# Shield_Dropscreen_LED_V_0_0.net
KiCad netlist of a schematic drawn in EasyEDA
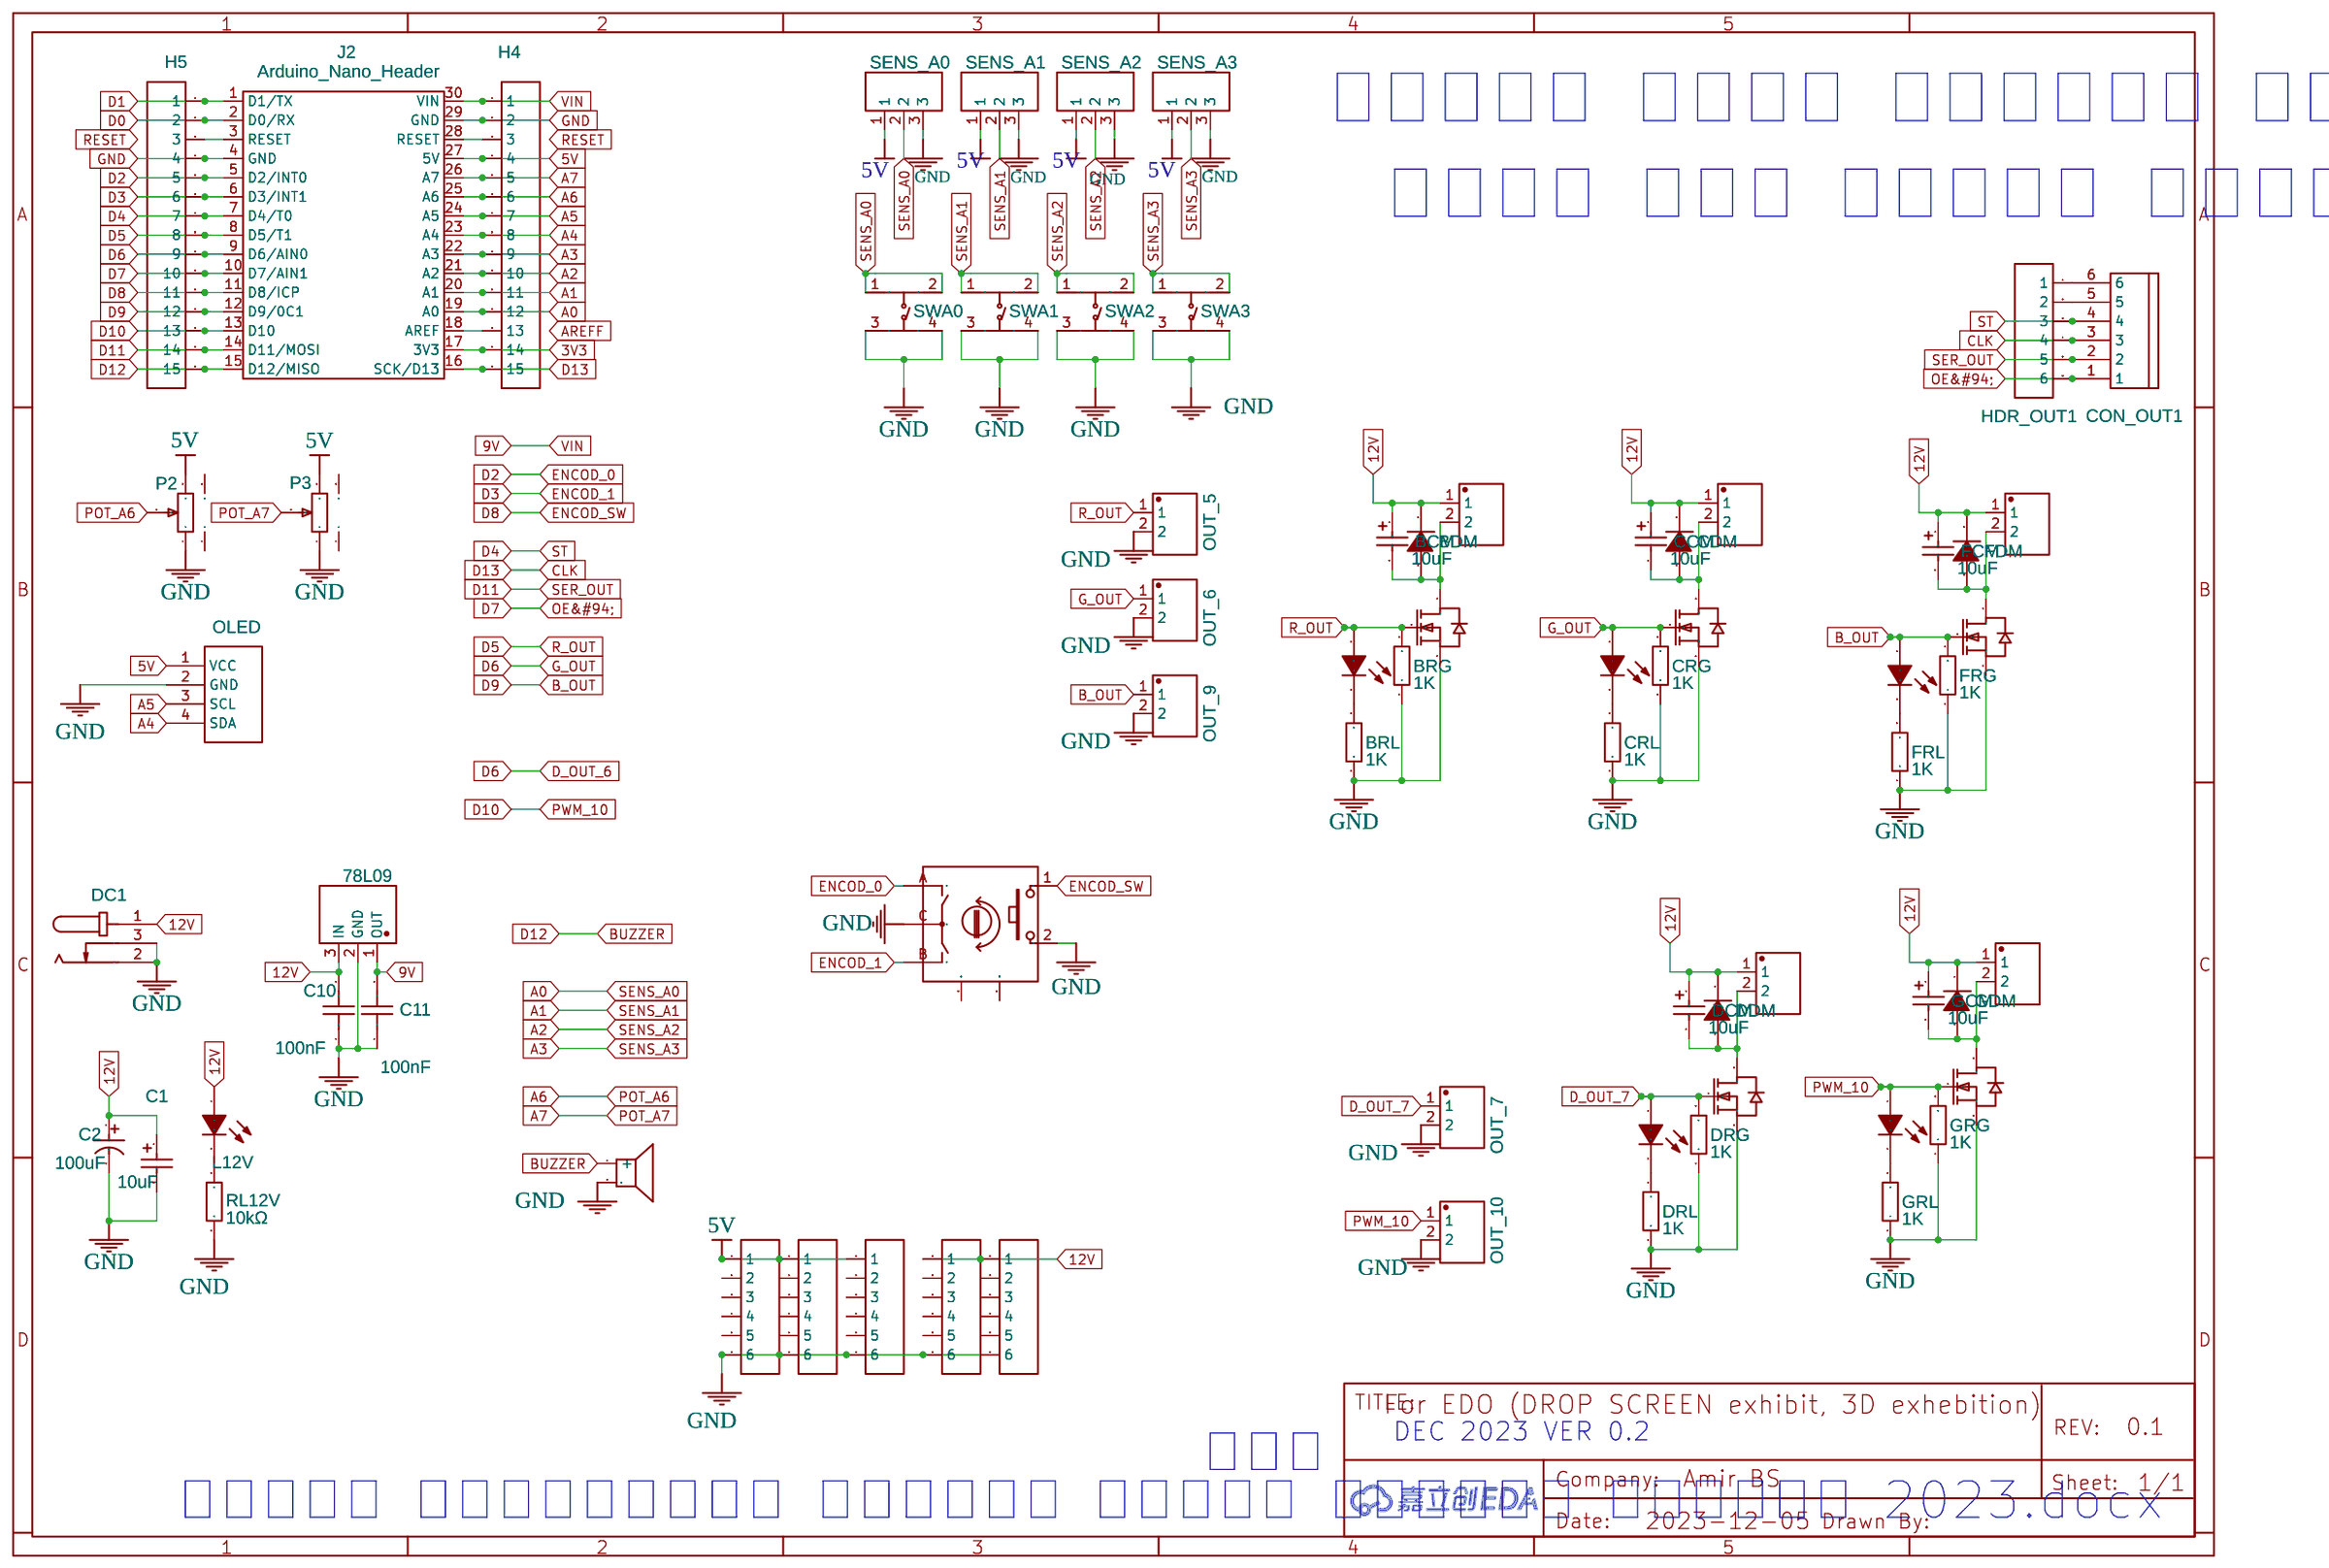
[diagram p0: schematic sheet]

(export (version "E")
  (design (tool "Eeschema 10.0.6"))
  (components
    (comp (ref "BCM")
      (value "10uF")
      (fields (field (name "Manufacturer Part") "TAJA106K016RNJ") (field (name "Manufacturer") "Kyocera AVX"))
      (libsource (lib "") (part "TAJA106K016RNJ"))
    )
    (comp (ref "BCON")
      (value "KF2510-2A")
      (fields (field (name "BOM_Supplier Part") "C27543"))
      (libsource (lib "") (part "KF2510-2A_1"))
    )
    (comp (ref "BDM")
      (value "1N4007")
      (fields (field (name "BOM_Manufacturer Part") "1N4007F") (field (name "BOM_Supplier Part") "C110856"))
      (libsource (lib "") (part "1N4007F_2"))
    )
    (comp (ref "BLD")
      (value "LED")
      (fields
        (field (name "BOM_Manufacturer Part") "19-217/BHC-ZL1M2RY/3T")
        (field (name "BOM_Supplier Part") "C72041")
      )
      (libsource (lib "") (part "19-217/BHC-ZL1M2RY/3T_3"))
    )
    (comp (ref "BQ")
      (value "Q")
      (fields (field (name "BOM_Manufacturer Part") "AO3400") (field (name "BOM_Supplier Part") "C5224189"))
      (libsource (lib "") (part "JSM2302_4"))
    )
    (comp (ref "BRG")
      (value "1K")
      (fields
        (field (name "BOM_Manufacturer Part") "0603WAF1001T5E")
        (field (name "BOM_Supplier Part") "C21190")
      )
      (libsource (lib "") (part "0603WAF1001T5E"))
    )
    (comp (ref "BRL")
      (value "1K")
      (fields
        (field (name "BOM_Manufacturer Part") "0603WAF1001T5E")
        (field (name "BOM_Supplier Part") "C21190")
      )
      (libsource (lib "") (part "0603WAF1001T5E_8"))
    )
    (comp (ref "BUZZER1")
      (value "BUZZER-12X9")
      (fields (field (name "Manufacturer Part") "buzzer-12X9"))
      (libsource (lib "") (part "BUZZER-12X9"))
    )
    (comp (ref "C1")
      (value "10uF")
      (fields (field (name "Manufacturer Part") "TAJA106K016RNJ") (field (name "Manufacturer") "Kyocera AVX"))
      (libsource (lib "") (part "TAJA106K016RNJ_4"))
    )
    (comp (ref "C2")
      (value "100uF")
      (fields
        (field (name "Manufacturer Part") "KM107M035E11RR0VH2FP0")
        (field (name "Manufacturer") "CX(承兴)")
      )
      (libsource (lib "") (part "100uF 35V 6.3*11"))
    )
    (comp (ref "C10")
      (value "100nF")
      (fields
        (field (name "Manufacturer Part") "CC0603KRX7R9BB104")
        (field (name "Manufacturer") "YAGEO(国巨)")
      )
      (libsource (lib "") (part "CC0603KRX7R9BB104"))
    )
    (comp (ref "C11")
      (value "100nF")
      (fields
        (field (name "Manufacturer Part") "CC0603KRX7R9BB104")
        (field (name "Manufacturer") "YAGEO(国巨)")
      )
      (libsource (lib "") (part "CC0603KRX7R9BB104"))
    )
    (comp (ref "CCM")
      (value "10uF")
      (fields (field (name "Manufacturer Part") "TAJA106K016RNJ") (field (name "Manufacturer") "Kyocera AVX"))
      (libsource (lib "") (part "TAJA106K016RNJ_3"))
    )
    (comp (ref "CCON")
      (value "KF2510-2A")
      (fields (field (name "BOM_Supplier Part") "C27543"))
      (libsource (lib "") (part "KF2510-2A_5"))
    )
    (comp (ref "CDM")
      (value "1N4007")
      (fields (field (name "BOM_Manufacturer Part") "1N4007F") (field (name "BOM_Supplier Part") "C110856"))
      (libsource (lib "") (part "1N4007F_3"))
    )
    (comp (ref "CLD")
      (value "LED")
      (fields
        (field (name "BOM_Manufacturer Part") "19-217/BHC-ZL1M2RY/3T")
        (field (name "BOM_Supplier Part") "C72041")
      )
      (libsource (lib "") (part "19-217/BHC-ZL1M2RY/3T"))
    )
    (comp (ref "CON_OUT1")
      (value "CON6")
      (fields (field (name "BOM_Manufacturer Part") "XH-6AW") (field (name "BOM_Supplier Part") "C8876"))
      (libsource (lib "") (part "XH-6AW_C8876"))
    )
    (comp (ref "CQ")
      (value "Q")
      (fields (field (name "BOM_Manufacturer Part") "AO3400") (field (name "BOM_Supplier Part") "C5224189"))
      (libsource (lib "") (part "JSM2302"))
    )
    (comp (ref "CRG")
      (value "1K")
      (fields
        (field (name "BOM_Manufacturer Part") "0603WAF1001T5E")
        (field (name "BOM_Supplier Part") "C21190")
      )
      (libsource (lib "") (part "0603WAF1001T5E_1"))
    )
    (comp (ref "CRL")
      (value "1K")
      (fields
        (field (name "BOM_Manufacturer Part") "0603WAF1001T5E")
        (field (name "BOM_Supplier Part") "C21190")
      )
      (libsource (lib "") (part "0603WAF1001T5E_7"))
    )
    (comp (ref "DC1")
      (value "DC")
      (fields
        (field (name "BOM_Manufacturer Part") "DC005-2.0MM")
        (field (name "BOM_Supplier Part") "C111567")
      )
      (libsource (lib "") (part "DC005-2.0MM"))
    )
    (comp (ref "DCM")
      (value "10uF")
      (fields (field (name "Manufacturer Part") "TAJA106K016RNJ") (field (name "Manufacturer") "Kyocera AVX"))
      (libsource (lib "") (part "TAJA106K016RNJ_1"))
    )
    (comp (ref "DCON")
      (value "KF2510-2A")
      (fields (field (name "BOM_Supplier Part") "C27543"))
      (libsource (lib "") (part "KF2510-2A_3"))
    )
    (comp (ref "DDM")
      (value "1N4007")
      (fields (field (name "BOM_Manufacturer Part") "1N4007F") (field (name "BOM_Supplier Part") "C110856"))
      (libsource (lib "") (part "1N4007F"))
    )
    (comp (ref "DLD")
      (value "LED")
      (fields
        (field (name "BOM_Manufacturer Part") "19-217/BHC-ZL1M2RY/3T")
        (field (name "BOM_Supplier Part") "C72041")
      )
      (libsource (lib "") (part "19-217/BHC-ZL1M2RY/3T_5"))
    )
    (comp (ref "DQ")
      (value "Q")
      (fields (field (name "BOM_Manufacturer Part") "AO3400") (field (name "BOM_Supplier Part") "C5224189"))
      (libsource (lib "") (part "JSM2302_2"))
    )
    (comp (ref "DRG")
      (value "1K")
      (fields
        (field (name "BOM_Manufacturer Part") "0603WAF1001T5E")
        (field (name "BOM_Supplier Part") "C21190")
      )
      (libsource (lib "") (part "0603WAF1001T5E_3"))
    )
    (comp (ref "DRL")
      (value "1K")
      (fields
        (field (name "BOM_Manufacturer Part") "0603WAF1001T5E")
        (field (name "BOM_Supplier Part") "C21190")
      )
      (libsource (lib "") (part "0603WAF1001T5E_4"))
    )
    (comp (ref "FCM")
      (value "10uF")
      (fields (field (name "Manufacturer Part") "TAJA106K016RNJ") (field (name "Manufacturer") "Kyocera AVX"))
      (libsource (lib "") (part "TAJA106K016RNJ_2"))
    )
    (comp (ref "FCON")
      (value "KF2510-2A")
      (fields (field (name "BOM_Supplier Part") "C27543"))
      (libsource (lib "") (part "KF2510-2A_2"))
    )
    (comp (ref "FDM")
      (value "1N4007")
      (fields (field (name "BOM_Manufacturer Part") "1N4007F") (field (name "BOM_Supplier Part") "C110856"))
      (libsource (lib "") (part "1N4007F_4"))
    )
    (comp (ref "FLD")
      (value "LED")
      (fields
        (field (name "BOM_Manufacturer Part") "19-217/BHC-ZL1M2RY/3T")
        (field (name "BOM_Supplier Part") "C72041")
      )
      (libsource (lib "") (part "19-217/BHC-ZL1M2RY/3T_1"))
    )
    (comp (ref "FQ")
      (value "Q")
      (fields (field (name "BOM_Manufacturer Part") "AO3400") (field (name "BOM_Supplier Part") "C5224189"))
      (libsource (lib "") (part "JSM2302_1"))
    )
    (comp (ref "FRG")
      (value "1K")
      (fields
        (field (name "BOM_Manufacturer Part") "0603WAF1001T5E")
        (field (name "BOM_Supplier Part") "C21190")
      )
      (libsource (lib "") (part "0603WAF1001T5E_9"))
    )
    (comp (ref "FRL")
      (value "1K")
      (fields
        (field (name "BOM_Manufacturer Part") "0603WAF1001T5E")
        (field (name "BOM_Supplier Part") "C21190")
      )
      (libsource (lib "") (part "0603WAF1001T5E_2"))
    )
    (comp (ref "GCM")
      (value "10uF")
      (fields (field (name "Manufacturer Part") "TAJA106K016RNJ") (field (name "Manufacturer") "Kyocera AVX"))
      (libsource (lib "") (part "TAJA106K016RNJ_5"))
    )
    (comp (ref "GCON")
      (value "KF2510-2A")
      (fields (field (name "BOM_Supplier Part") "C27543"))
      (libsource (lib "") (part "KF2510-2A"))
    )
    (comp (ref "GDM")
      (value "1N4007")
      (fields (field (name "BOM_Manufacturer Part") "1N4007F") (field (name "BOM_Supplier Part") "C110856"))
      (libsource (lib "") (part "1N4007F_1"))
    )
    (comp (ref "GLD")
      (value "LED")
      (fields
        (field (name "BOM_Manufacturer Part") "19-217/BHC-ZL1M2RY/3T")
        (field (name "BOM_Supplier Part") "C72041")
      )
      (libsource (lib "") (part "19-217/BHC-ZL1M2RY/3T_4"))
    )
    (comp (ref "GQ")
      (value "Q")
      (fields (field (name "BOM_Manufacturer Part") "AO3400") (field (name "BOM_Supplier Part") "C5224189"))
      (libsource (lib "") (part "JSM2302_3"))
    )
    (comp (ref "GRG")
      (value "1K")
      (fields
        (field (name "BOM_Manufacturer Part") "0603WAF1001T5E")
        (field (name "BOM_Supplier Part") "C21190")
      )
      (libsource (lib "") (part "0603WAF1001T5E_5"))
    )
    (comp (ref "GRL")
      (value "1K")
      (fields
        (field (name "BOM_Manufacturer Part") "0603WAF1001T5E")
        (field (name "BOM_Supplier Part") "C21190")
      )
      (libsource (lib "") (part "0603WAF1001T5E_6"))
    )
    (comp (ref "H1")
      (value "HDR-F-2.54_1x6")
      (fields (field (name "BOM_Supplier Part") "C40877"))
      (libsource (lib "") (part "HDR-F-2.54_1x6"))
    )
    (comp (ref "H2")
      (value "HDR-F-2.54_1x6")
      (fields (field (name "BOM_Supplier Part") "C40877"))
      (libsource (lib "") (part "HDR-F-2.54_1x6"))
    )
    (comp (ref "H3")
      (value "HDR-F-2.54_1x6")
      (fields (field (name "BOM_Supplier Part") "C40877"))
      (libsource (lib "") (part "HDR-F-2.54_1x6"))
    )
    (comp (ref "H4")
      (value "HDR-F-2.54_1x15")
      (fields (field (name "BOM_Supplier Part") "C124408"))
      (libsource (lib "") (part "HDR-F-2.54_1x15_1"))
    )
    (comp (ref "H5")
      (value "HDR-F-2.54_1x15")
      (fields (field (name "BOM_Supplier Part") "C124408"))
      (libsource (lib "") (part "HDR-F-2.54_1x15"))
    )
    (comp (ref "H6")
      (value "HDR-F-2.54_1x6")
      (fields (field (name "BOM_Supplier Part") "C40877"))
      (libsource (lib "") (part "HDR-F-2.54_1x6"))
    )
    (comp (ref "H11")
      (value "HDR-F-2.54_1x6")
      (fields (field (name "BOM_Supplier Part") "C40877"))
      (libsource (lib "") (part "HDR-F-2.54_1x6"))
    )
    (comp (ref "HDR_OUT1")
      (value "HDR6")
      (fields (field (name "BOM_Supplier Part") "C190819"))
      (libsource (lib "") (part "HDR-M-2.54_1x6"))
    )
    (comp (ref "J2") (value "Arduino_Nano_Header") (libsource (lib "") (part "Arduino_Nano_Header")))
    (comp (ref "L12V")
      (value "LED")
      (fields
        (field (name "BOM_Manufacturer Part") "19-217/BHC-ZL1M2RY/3T")
        (field (name "BOM_Supplier Part") "C72041")
      )
      (libsource (lib "") (part "19-217/BHC-ZL1M2RY/3T_2"))
    )
    (comp (ref "OLED")
      (value "1.3 inch OLED SSH1106 I2C 128x64 copy")
      (libsource (lib "") (part "1.3 inch OLED SSH1106 I2C 128x64 copy"))
    )
    (comp (ref "OUT_5")
      (value "KF2510-2A")
      (fields (field (name "BOM_Supplier Part") "C27543"))
      (libsource (lib "") (part "KF2510-2A_4"))
    )
    (comp (ref "OUT_6")
      (value "KF2510-2A")
      (fields (field (name "BOM_Supplier Part") "C27543"))
      (libsource (lib "") (part "KF2510-2A_4"))
    )
    (comp (ref "OUT_7")
      (value "KF2510-2A")
      (fields (field (name "BOM_Supplier Part") "C27543"))
      (libsource (lib "") (part "KF2510-2A_4"))
    )
    (comp (ref "OUT_9")
      (value "KF2510-2A")
      (fields (field (name "BOM_Supplier Part") "C27543"))
      (libsource (lib "") (part "KF2510-2A_4"))
    )
    (comp (ref "OUT_10")
      (value "KF2510-2A")
      (fields (field (name "BOM_Supplier Part") "C27543"))
      (libsource (lib "") (part "KF2510-2A_4"))
    )
    (comp (ref "P2")
      (value "长柄旋转电位器")
      (fields (field (name "BOM_Supplier Part") "C2874842"))
      (libsource (lib "") (part "长柄旋转电位器"))
    )
    (comp (ref "P3")
      (value "长柄旋转电位器")
      (fields (field (name "BOM_Supplier Part") "C2874842"))
      (libsource (lib "") (part "长柄旋转电位器"))
    )
    (comp (ref "RL12V")
      (value "10kΩ")
      (fields
        (field (name "BOM_Manufacturer Part") "0603WAF1002T5E")
        (field (name "BOM_Supplier Part") "C25804")
      )
      (libsource (lib "") (part "0603WAF1002T5E"))
    )
    (comp (ref "SENS_A0")
      (value "FK2510")
      (fields (field (name "Manufacturer Part") "2510-3A") (field (name "Manufacturer") "BOOMELE(博穆精密)"))
      (libsource (lib "") (part "kf2510_3A"))
    )
    (comp (ref "SENS_A1")
      (value "FK2510")
      (fields (field (name "Manufacturer Part") "2510-3A") (field (name "Manufacturer") "BOOMELE(博穆精密)"))
      (libsource (lib "") (part "kf2510_3A"))
    )
    (comp (ref "SENS_A2")
      (value "FK2510")
      (fields (field (name "Manufacturer Part") "2510-3A") (field (name "Manufacturer") "BOOMELE(博穆精密)"))
      (libsource (lib "") (part "kf2510_3A"))
    )
    (comp (ref "SENS_A3")
      (value "FK2510")
      (fields (field (name "Manufacturer Part") "2510-3A") (field (name "Manufacturer") "BOOMELE(博穆精密)"))
      (libsource (lib "") (part "kf2510_3A"))
    )
    (comp (ref "SW1")
      (value "PEC11R-4015F-S0024")
      (fields (field (name "Manufacturer") "BOURNS"))
      (libsource (lib "") (part "PEC11R-4015F-S0024"))
    )
    (comp (ref "SWA0")
      (value "TC-6610-7-160G")
      (fields (field (name "Manufacturer") "HCTL(华灿天禄)"))
      (libsource (lib "") (part "TC-6610-7-160G"))
    )
    (comp (ref "SWA1")
      (value "TC-6610-7-160G")
      (fields (field (name "Manufacturer") "HCTL(华灿天禄)"))
      (libsource (lib "") (part "TC-6610-7-160G"))
    )
    (comp (ref "SWA2")
      (value "TC-6610-7-160G")
      (fields (field (name "Manufacturer") "HCTL(华灿天禄)"))
      (libsource (lib "") (part "TC-6610-7-160G"))
    )
    (comp (ref "SWA3")
      (value "TC-6610-7-160G")
      (fields (field (name "Manufacturer") "HCTL(华灿天禄)"))
      (libsource (lib "") (part "TC-6610-7-160G"))
    )
    (comp (ref "U5")
      (value "78L09")
      (fields (field (name "Manufacturer Part") "78L09U 78L09") (field (name "Manufacturer") "CBI(创基)"))
      (libsource (lib "") (part "78L09U 78L09"))
    )
  )
  (nets
    (net (code "1") (name "3V3") (class "Default")
      (node (ref "H4") (pin "14") (pinfunction "14_14") (pintype "unspecified"))
      (node (ref "J2") (pin "17") (pinfunction "3V3_17") (pintype "unspecified"))
    )
    (net (code "2") (name "5V") (class "Default")
      (node (ref "H1") (pin "1") (pinfunction "1_1") (pintype "input"))
      (node (ref "H2") (pin "1") (pinfunction "1_1") (pintype "input"))
      (node (ref "H3") (pin "1") (pinfunction "1_1") (pintype "input"))
      (node (ref "H4") (pin "4") (pinfunction "4_4") (pintype "unspecified"))
      (node (ref "J2") (pin "27") (pinfunction "5V_27") (pintype "unspecified"))
      (node (ref "OLED") (pin "1") (pinfunction "VCC_1") (pintype "passive"))
      (node (ref "P2") (pin "3") (pinfunction "3_3") (pintype "input"))
      (node (ref "P3") (pin "3") (pinfunction "3_3") (pintype "input"))
      (node (ref "SENS_A0") (pin "1") (pinfunction "1_1") (pintype "unspecified"))
      (node (ref "SENS_A1") (pin "1") (pinfunction "1_1") (pintype "unspecified"))
      (node (ref "SENS_A2") (pin "1") (pinfunction "1_1") (pintype "unspecified"))
      (node (ref "SENS_A3") (pin "1") (pinfunction "1_1") (pintype "unspecified"))
    )
    (net (code "3") (name "9V") (class "Default")
      (node (ref "C11") (pin "2") (pinfunction "2_2") (pintype "unspecified"))
      (node (ref "H4") (pin "1") (pinfunction "1_1") (pintype "unspecified"))
      (node (ref "J2") (pin "30") (pinfunction "VIN_30") (pintype "unspecified"))
      (node (ref "U5") (pin "1") (pinfunction "OUT_1") (pintype "unspecified"))
    )
    (net (code "4") (name "12V") (class "Default")
      (node (ref "BCM") (pin "1") (pinfunction "1_1") (pintype "input"))
      (node (ref "BCON") (pin "1") (pinfunction "1_1") (pintype "unspecified"))
      (node (ref "BDM") (pin "1") (pinfunction "C_1") (pintype "unspecified"))
      (node (ref "C1") (pin "1") (pinfunction "1_1") (pintype "input"))
      (node (ref "C10") (pin "2") (pinfunction "2_2") (pintype "unspecified"))
      (node (ref "C2") (pin "1") (pinfunction "1_1") (pintype "input"))
      (node (ref "CCM") (pin "1") (pinfunction "1_1") (pintype "input"))
      (node (ref "CCON") (pin "1") (pinfunction "1_1") (pintype "unspecified"))
      (node (ref "CDM") (pin "1") (pinfunction "C_1") (pintype "unspecified"))
      (node (ref "DC1") (pin "1") (pinfunction "1_1") (pintype "unspecified"))
      (node (ref "DCM") (pin "1") (pinfunction "1_1") (pintype "input"))
      (node (ref "DCON") (pin "1") (pinfunction "1_1") (pintype "unspecified"))
      (node (ref "DDM") (pin "1") (pinfunction "C_1") (pintype "unspecified"))
      (node (ref "FCM") (pin "1") (pinfunction "1_1") (pintype "input"))
      (node (ref "FCON") (pin "1") (pinfunction "1_1") (pintype "unspecified"))
      (node (ref "FDM") (pin "1") (pinfunction "C_1") (pintype "unspecified"))
      (node (ref "GCM") (pin "1") (pinfunction "1_1") (pintype "input"))
      (node (ref "GCON") (pin "1") (pinfunction "1_1") (pintype "unspecified"))
      (node (ref "GDM") (pin "1") (pinfunction "C_1") (pintype "unspecified"))
      (node (ref "H11") (pin "1") (pinfunction "1_1") (pintype "input"))
      (node (ref "H6") (pin "1") (pinfunction "1_1") (pintype "input"))
      (node (ref "L12V") (pin "1") (pinfunction "A_1") (pintype "input"))
      (node (ref "U5") (pin "3") (pinfunction "IN_3") (pintype "unspecified"))
    )
    (net (code "5") (name "A0") (class "Default")
      (node (ref "H4") (pin "12") (pinfunction "12_12") (pintype "unspecified"))
      (node (ref "J2") (pin "19") (pinfunction "A0_19") (pintype "unspecified"))
      (node (ref "SENS_A0") (pin "2") (pinfunction "2_2") (pintype "unspecified"))
      (node (ref "SWA0") (pin "1") (pinfunction "1_1") (pintype "unspecified"))
      (node (ref "SWA0") (pin "2") (pinfunction "2_2") (pintype "unspecified"))
    )
    (net (code "6") (name "A1") (class "Default")
      (node (ref "H4") (pin "11") (pinfunction "11_11") (pintype "unspecified"))
      (node (ref "J2") (pin "20") (pinfunction "A1_20") (pintype "unspecified"))
      (node (ref "SENS_A1") (pin "2") (pinfunction "2_2") (pintype "unspecified"))
      (node (ref "SWA1") (pin "1") (pinfunction "1_1") (pintype "unspecified"))
      (node (ref "SWA1") (pin "2") (pinfunction "2_2") (pintype "unspecified"))
    )
    (net (code "7") (name "A2") (class "Default")
      (node (ref "H4") (pin "10") (pinfunction "10_10") (pintype "unspecified"))
      (node (ref "J2") (pin "21") (pinfunction "A2_21") (pintype "unspecified"))
      (node (ref "SENS_A2") (pin "2") (pinfunction "2_2") (pintype "unspecified"))
      (node (ref "SWA2") (pin "1") (pinfunction "1_1") (pintype "unspecified"))
      (node (ref "SWA2") (pin "2") (pinfunction "2_2") (pintype "unspecified"))
    )
    (net (code "8") (name "A3") (class "Default")
      (node (ref "H4") (pin "9") (pinfunction "9_9") (pintype "unspecified"))
      (node (ref "J2") (pin "22") (pinfunction "A3_22") (pintype "unspecified"))
      (node (ref "SENS_A3") (pin "2") (pinfunction "2_2") (pintype "unspecified"))
      (node (ref "SWA3") (pin "1") (pinfunction "1_1") (pintype "unspecified"))
      (node (ref "SWA3") (pin "2") (pinfunction "2_2") (pintype "unspecified"))
    )
    (net (code "9") (name "A4") (class "Default")
      (node (ref "H4") (pin "8") (pinfunction "8_8") (pintype "unspecified"))
      (node (ref "J2") (pin "23") (pinfunction "A4_23") (pintype "unspecified"))
      (node (ref "OLED") (pin "4") (pinfunction "SDA_4") (pintype "bidirectional"))
    )
    (net (code "10") (name "A5") (class "Default")
      (node (ref "H4") (pin "7") (pinfunction "7_7") (pintype "unspecified"))
      (node (ref "J2") (pin "24") (pinfunction "A5_24") (pintype "unspecified"))
      (node (ref "OLED") (pin "3") (pinfunction "SCL_3") (pintype "bidirectional"))
    )
    (net (code "11") (name "A6") (class "Default")
      (node (ref "H4") (pin "6") (pinfunction "6_6") (pintype "unspecified"))
      (node (ref "J2") (pin "25") (pinfunction "A6_25") (pintype "unspecified"))
      (node (ref "P2") (pin "2") (pinfunction "2_2") (pintype "input"))
    )
    (net (code "12") (name "A7") (class "Default")
      (node (ref "H4") (pin "5") (pinfunction "5_5") (pintype "unspecified"))
      (node (ref "J2") (pin "26") (pinfunction "A7_26") (pintype "unspecified"))
      (node (ref "P3") (pin "2") (pinfunction "2_2") (pintype "input"))
    )
    (net (code "14") (name "BUZZER") (class "Default")
      (node (ref "BUZZER1") (pin "1") (pinfunction "+_1") (pintype "unspecified"))
      (node (ref "H5") (pin "15") (pinfunction "15_15") (pintype "unspecified"))
      (node (ref "J2") (pin "15") (pinfunction "D12/MISO_15") (pintype "unspecified"))
    )
    (net (code "15") (name "B_OUT") (class "Default")
      (node (ref "FLD") (pin "1") (pinfunction "A_1") (pintype "input"))
      (node (ref "FQ") (pin "1") (pinfunction "G_1") (pintype "unspecified"))
      (node (ref "FRG") (pin "2") (pinfunction "2_2") (pintype "input"))
      (node (ref "H5") (pin "12") (pinfunction "12_12") (pintype "unspecified"))
      (node (ref "J2") (pin "12") (pinfunction "D9/0C1_12") (pintype "unspecified"))
      (node (ref "OUT_9") (pin "1") (pinfunction "1_1") (pintype "unspecified"))
    )
    (net (code "16") (name "CLK") (class "Default")
      (node (ref "CON_OUT1") (pin "3") (pinfunction "3_3") (pintype "unspecified"))
      (node (ref "H4") (pin "15") (pinfunction "15_15") (pintype "unspecified"))
      (node (ref "HDR_OUT1") (pin "4") (pinfunction "4_4") (pintype "input"))
      (node (ref "J2") (pin "16") (pinfunction "SCK/D13_16") (pintype "unspecified"))
    )
    (net (code "17") (name "D0") (class "Default")
      (node (ref "H5") (pin "2") (pinfunction "2_2") (pintype "unspecified"))
      (node (ref "J2") (pin "2") (pinfunction "D0/RX_2") (pintype "unspecified"))
    )
    (net (code "18") (name "D1") (class "Default")
      (node (ref "H5") (pin "1") (pinfunction "1_1") (pintype "unspecified"))
      (node (ref "J2") (pin "1") (pinfunction "D1/TX_1") (pintype "unspecified"))
    )
    (net (code "19") (name "D2") (class "Default")
      (node (ref "H5") (pin "5") (pinfunction "5_5") (pintype "unspecified"))
      (node (ref "J2") (pin "5") (pinfunction "D2/INT0_5") (pintype "unspecified"))
      (node (ref "SW1") (pin "A") (pinfunction "A_A") (pintype "unspecified"))
    )
    (net (code "20") (name "D3") (class "Default")
      (node (ref "H5") (pin "6") (pinfunction "6_6") (pintype "unspecified"))
      (node (ref "J2") (pin "6") (pinfunction "D3/INT1_6") (pintype "unspecified"))
      (node (ref "SW1") (pin "B") (pinfunction "B_B") (pintype "unspecified"))
    )
    (net (code "21") (name "D4") (class "Default")
      (node (ref "CON_OUT1") (pin "4") (pinfunction "4_4") (pintype "unspecified"))
      (node (ref "H5") (pin "7") (pinfunction "7_7") (pintype "unspecified"))
      (node (ref "HDR_OUT1") (pin "3") (pinfunction "3_3") (pintype "input"))
      (node (ref "J2") (pin "7") (pinfunction "D4/T0_7") (pintype "unspecified"))
    )
    (net (code "22") (name "D5") (class "Default")
      (node (ref "BLD") (pin "1") (pinfunction "A_1") (pintype "input"))
      (node (ref "BQ") (pin "1") (pinfunction "G_1") (pintype "unspecified"))
      (node (ref "BRG") (pin "2") (pinfunction "2_2") (pintype "input"))
      (node (ref "H5") (pin "8") (pinfunction "8_8") (pintype "unspecified"))
      (node (ref "J2") (pin "8") (pinfunction "D5/T1_8") (pintype "unspecified"))
      (node (ref "OUT_5") (pin "1") (pinfunction "1_1") (pintype "unspecified"))
    )
    (net (code "23") (name "D6") (class "Default")
      (node (ref "CLD") (pin "1") (pinfunction "A_1") (pintype "input"))
      (node (ref "CQ") (pin "1") (pinfunction "G_1") (pintype "unspecified"))
      (node (ref "CRG") (pin "2") (pinfunction "2_2") (pintype "input"))
      (node (ref "H5") (pin "9") (pinfunction "9_9") (pintype "unspecified"))
      (node (ref "J2") (pin "9") (pinfunction "D6/AIN0_9") (pintype "unspecified"))
      (node (ref "OUT_6") (pin "1") (pinfunction "1_1") (pintype "unspecified"))
    )
    (net (code "24") (name "D7") (class "Default")
      (node (ref "CON_OUT1") (pin "1") (pinfunction "1_1") (pintype "unspecified"))
      (node (ref "H5") (pin "10") (pinfunction "10_10") (pintype "unspecified"))
      (node (ref "HDR_OUT1") (pin "6") (pinfunction "6_6") (pintype "input"))
      (node (ref "J2") (pin "10") (pinfunction "D7/AIN1_10") (pintype "unspecified"))
    )
    (net (code "25") (name "D8") (class "Default")
      (node (ref "H5") (pin "11") (pinfunction "11_11") (pintype "unspecified"))
      (node (ref "J2") (pin "11") (pinfunction "D8/ICP_11") (pintype "unspecified"))
      (node (ref "SW1") (pin "1") (pinfunction "1_1") (pintype "unspecified"))
    )
    (net (code "26") (name "D10") (class "Default")
      (node (ref "GLD") (pin "1") (pinfunction "A_1") (pintype "input"))
      (node (ref "GQ") (pin "1") (pinfunction "G_1") (pintype "unspecified"))
      (node (ref "GRG") (pin "2") (pinfunction "2_2") (pintype "input"))
      (node (ref "H5") (pin "13") (pinfunction "13_13") (pintype "unspecified"))
      (node (ref "J2") (pin "13") (pinfunction "D10_13") (pintype "unspecified"))
      (node (ref "OUT_10") (pin "1") (pinfunction "1_1") (pintype "unspecified"))
    )
    (net (code "27") (name "D11") (class "Default")
      (node (ref "CON_OUT1") (pin "2") (pinfunction "2_2") (pintype "unspecified"))
      (node (ref "H5") (pin "14") (pinfunction "14_14") (pintype "unspecified"))
      (node (ref "HDR_OUT1") (pin "5") (pinfunction "5_5") (pintype "input"))
      (node (ref "J2") (pin "14") (pinfunction "D11/MOSI_14") (pintype "unspecified"))
    )
    (net (code "28") (name "D_OUT_7") (class "Default")
      (node (ref "DLD") (pin "1") (pinfunction "A_1") (pintype "input"))
      (node (ref "DQ") (pin "1") (pinfunction "G_1") (pintype "unspecified"))
      (node (ref "DRG") (pin "2") (pinfunction "2_2") (pintype "input"))
      (node (ref "OUT_7") (pin "1") (pinfunction "1_1") (pintype "unspecified"))
    )
    (net (code "29") (name "GND") (class "Default")
      (node (ref "BQ") (pin "2") (pinfunction "S_2") (pintype "unspecified"))
      (node (ref "BRG") (pin "1") (pinfunction "1_1") (pintype "input"))
      (node (ref "BRL") (pin "1") (pinfunction "1_1") (pintype "input"))
      (node (ref "BUZZER1") (pin "2") (pinfunction "2_2") (pintype "unspecified"))
      (node (ref "C1") (pin "2") (pinfunction "2_2") (pintype "input"))
      (node (ref "C10") (pin "1") (pinfunction "1_1") (pintype "unspecified"))
      (node (ref "C11") (pin "1") (pinfunction "1_1") (pintype "unspecified"))
      (node (ref "C2") (pin "2") (pinfunction "2_2") (pintype "input"))
      (node (ref "CQ") (pin "2") (pinfunction "S_2") (pintype "unspecified"))
      (node (ref "CRG") (pin "1") (pinfunction "1_1") (pintype "input"))
      (node (ref "CRL") (pin "1") (pinfunction "1_1") (pintype "input"))
      (node (ref "DC1") (pin "2") (pinfunction "2_2") (pintype "unspecified"))
      (node (ref "DC1") (pin "3") (pinfunction "3_3") (pintype "unspecified"))
      (node (ref "DQ") (pin "2") (pinfunction "S_2") (pintype "unspecified"))
      (node (ref "DRG") (pin "1") (pinfunction "1_1") (pintype "input"))
      (node (ref "DRL") (pin "1") (pinfunction "1_1") (pintype "input"))
      (node (ref "FQ") (pin "2") (pinfunction "S_2") (pintype "unspecified"))
      (node (ref "FRG") (pin "1") (pinfunction "1_1") (pintype "input"))
      (node (ref "FRL") (pin "1") (pinfunction "1_1") (pintype "input"))
      (node (ref "GQ") (pin "2") (pinfunction "S_2") (pintype "unspecified"))
      (node (ref "GRG") (pin "1") (pinfunction "1_1") (pintype "input"))
      (node (ref "GRL") (pin "1") (pinfunction "1_1") (pintype "input"))
      (node (ref "H1") (pin "6") (pinfunction "6_6") (pintype "input"))
      (node (ref "H11") (pin "6") (pinfunction "6_6") (pintype "input"))
      (node (ref "H2") (pin "6") (pinfunction "6_6") (pintype "input"))
      (node (ref "H3") (pin "6") (pinfunction "6_6") (pintype "input"))
      (node (ref "H4") (pin "2") (pinfunction "2_2") (pintype "unspecified"))
      (node (ref "H5") (pin "4") (pinfunction "4_4") (pintype "unspecified"))
      (node (ref "H6") (pin "6") (pinfunction "6_6") (pintype "input"))
      (node (ref "J2") (pin "29") (pinfunction "GND_29") (pintype "unspecified"))
      (node (ref "J2") (pin "4") (pinfunction "GND_4") (pintype "unspecified"))
      (node (ref "OLED") (pin "2") (pinfunction "GND_2") (pintype "passive"))
      (node (ref "OUT_10") (pin "2") (pinfunction "2_2") (pintype "unspecified"))
      (node (ref "OUT_5") (pin "2") (pinfunction "2_2") (pintype "unspecified"))
      (node (ref "OUT_6") (pin "2") (pinfunction "2_2") (pintype "unspecified"))
      (node (ref "OUT_7") (pin "2") (pinfunction "2_2") (pintype "unspecified"))
      (node (ref "OUT_9") (pin "2") (pinfunction "2_2") (pintype "unspecified"))
      (node (ref "P2") (pin "1") (pinfunction "1_1") (pintype "input"))
      (node (ref "P3") (pin "1") (pinfunction "1_1") (pintype "input"))
      (node (ref "RL12V") (pin "2") (pinfunction "2_2") (pintype "input"))
      (node (ref "SENS_A0") (pin "3") (pinfunction "3_3") (pintype "unspecified"))
      (node (ref "SENS_A1") (pin "3") (pinfunction "3_3") (pintype "unspecified"))
      (node (ref "SENS_A2") (pin "3") (pinfunction "3_3") (pintype "unspecified"))
      (node (ref "SENS_A3") (pin "3") (pinfunction "3_3") (pintype "unspecified"))
      (node (ref "SW1") (pin "2") (pinfunction "2_2") (pintype "unspecified"))
      (node (ref "SW1") (pin "C") (pinfunction "C_C") (pintype "unspecified"))
      (node (ref "SWA0") (pin "3") (pinfunction "3_3") (pintype "unspecified"))
      (node (ref "SWA0") (pin "4") (pinfunction "4_4") (pintype "unspecified"))
      (node (ref "SWA1") (pin "3") (pinfunction "3_3") (pintype "unspecified"))
      (node (ref "SWA1") (pin "4") (pinfunction "4_4") (pintype "unspecified"))
      (node (ref "SWA2") (pin "3") (pinfunction "3_3") (pintype "unspecified"))
      (node (ref "SWA2") (pin "4") (pinfunction "4_4") (pintype "unspecified"))
      (node (ref "SWA3") (pin "3") (pinfunction "3_3") (pintype "unspecified"))
      (node (ref "SWA3") (pin "4") (pinfunction "4_4") (pintype "unspecified"))
      (node (ref "U5") (pin "2") (pinfunction "GND_2") (pintype "unspecified"))
    )
    (net (code "30") (name "Net-(BDM-A)") (class "Default")
      (node (ref "BCM") (pin "2") (pinfunction "2_2") (pintype "input"))
      (node (ref "BCON") (pin "2") (pinfunction "2_2") (pintype "unspecified"))
      (node (ref "BDM") (pin "2") (pinfunction "A_2") (pintype "unspecified"))
      (node (ref "BQ") (pin "3") (pinfunction "D_3") (pintype "unspecified"))
    )
    (net (code "31") (name "Net-(BLD-C)") (class "Default")
      (node (ref "BLD") (pin "2") (pinfunction "C_2") (pintype "input"))
      (node (ref "BRL") (pin "2") (pinfunction "2_2") (pintype "input"))
    )
    (net (code "32") (name "Net-(CDM-A)") (class "Default")
      (node (ref "CCM") (pin "2") (pinfunction "2_2") (pintype "input"))
      (node (ref "CCON") (pin "2") (pinfunction "2_2") (pintype "unspecified"))
      (node (ref "CDM") (pin "2") (pinfunction "A_2") (pintype "unspecified"))
      (node (ref "CQ") (pin "3") (pinfunction "D_3") (pintype "unspecified"))
    )
    (net (code "33") (name "Net-(CLD-C)") (class "Default")
      (node (ref "CLD") (pin "2") (pinfunction "C_2") (pintype "input"))
      (node (ref "CRL") (pin "2") (pinfunction "2_2") (pintype "input"))
    )
    (net (code "34") (name "Net-(CON_OUT1-Pad5)") (class "Default")
      (node (ref "CON_OUT1") (pin "5") (pinfunction "5_5") (pintype "unspecified"))
      (node (ref "HDR_OUT1") (pin "2") (pinfunction "2_2") (pintype "input"))
    )
    (net (code "35") (name "Net-(CON_OUT1-Pad6)") (class "Default")
      (node (ref "CON_OUT1") (pin "6") (pinfunction "6_6") (pintype "unspecified"))
      (node (ref "HDR_OUT1") (pin "1") (pinfunction "1_1") (pintype "input"))
    )
    (net (code "36") (name "Net-(DDM-A)") (class "Default")
      (node (ref "DCM") (pin "2") (pinfunction "2_2") (pintype "input"))
      (node (ref "DCON") (pin "2") (pinfunction "2_2") (pintype "unspecified"))
      (node (ref "DDM") (pin "2") (pinfunction "A_2") (pintype "unspecified"))
      (node (ref "DQ") (pin "3") (pinfunction "D_3") (pintype "unspecified"))
    )
    (net (code "37") (name "Net-(DLD-C)") (class "Default")
      (node (ref "DLD") (pin "2") (pinfunction "C_2") (pintype "input"))
      (node (ref "DRL") (pin "2") (pinfunction "2_2") (pintype "input"))
    )
    (net (code "38") (name "Net-(FDM-A)") (class "Default")
      (node (ref "FCM") (pin "2") (pinfunction "2_2") (pintype "input"))
      (node (ref "FCON") (pin "2") (pinfunction "2_2") (pintype "unspecified"))
      (node (ref "FDM") (pin "2") (pinfunction "A_2") (pintype "unspecified"))
      (node (ref "FQ") (pin "3") (pinfunction "D_3") (pintype "unspecified"))
    )
    (net (code "39") (name "Net-(FLD-C)") (class "Default")
      (node (ref "FLD") (pin "2") (pinfunction "C_2") (pintype "input"))
      (node (ref "FRL") (pin "2") (pinfunction "2_2") (pintype "input"))
    )
    (net (code "40") (name "Net-(GDM-A)") (class "Default")
      (node (ref "GCM") (pin "2") (pinfunction "2_2") (pintype "input"))
      (node (ref "GCON") (pin "2") (pinfunction "2_2") (pintype "unspecified"))
      (node (ref "GDM") (pin "2") (pinfunction "A_2") (pintype "unspecified"))
      (node (ref "GQ") (pin "3") (pinfunction "D_3") (pintype "unspecified"))
    )
    (net (code "41") (name "Net-(GLD-C)") (class "Default")
      (node (ref "GLD") (pin "2") (pinfunction "C_2") (pintype "input"))
      (node (ref "GRL") (pin "2") (pinfunction "2_2") (pintype "input"))
    )
    (net (code "42") (name "Net-(H4-Pad3)") (class "Default")
      (node (ref "H4") (pin "3") (pinfunction "3_3") (pintype "unspecified"))
      (node (ref "J2") (pin "28") (pinfunction "RESET_28") (pintype "unspecified"))
    )
    (net (code "43") (name "Net-(H5-Pad3)") (class "Default")
      (node (ref "H5") (pin "3") (pinfunction "3_3") (pintype "unspecified"))
      (node (ref "J2") (pin "3") (pinfunction "RESET_3") (pintype "unspecified"))
    )
    (net (code "44") (name "Net-(J2-AREF)") (class "Default")
      (node (ref "H4") (pin "13") (pinfunction "13_13") (pintype "unspecified"))
      (node (ref "J2") (pin "18") (pinfunction "AREF_18") (pintype "unspecified"))
    )
    (net (code "45") (name "Net-(L12V-C)") (class "Default")
      (node (ref "L12V") (pin "2") (pinfunction "C_2") (pintype "input"))
      (node (ref "RL12V") (pin "1") (pinfunction "1_1") (pintype "input"))
    )
    (net (code "47") (name "unconnected-(H1-Pad2)") (class "Default")
      (node (ref "H1") (pin "2") (pinfunction "2_2") (pintype "input"))
    )
    (net (code "48") (name "unconnected-(H1-Pad3)") (class "Default")
      (node (ref "H1") (pin "3") (pinfunction "3_3") (pintype "input"))
    )
    (net (code "49") (name "unconnected-(H1-Pad4)") (class "Default")
      (node (ref "H1") (pin "4") (pinfunction "4_4") (pintype "input"))
    )
    (net (code "50") (name "unconnected-(H1-Pad5)") (class "Default")
      (node (ref "H1") (pin "5") (pinfunction "5_5") (pintype "input"))
    )
    (net (code "51") (name "unconnected-(H2-Pad2)") (class "Default")
      (node (ref "H2") (pin "2") (pinfunction "2_2") (pintype "input"))
    )
    (net (code "52") (name "unconnected-(H2-Pad3)") (class "Default")
      (node (ref "H2") (pin "3") (pinfunction "3_3") (pintype "input"))
    )
    (net (code "53") (name "unconnected-(H2-Pad4)") (class "Default")
      (node (ref "H2") (pin "4") (pinfunction "4_4") (pintype "input"))
    )
    (net (code "54") (name "unconnected-(H2-Pad5)") (class "Default")
      (node (ref "H2") (pin "5") (pinfunction "5_5") (pintype "input"))
    )
    (net (code "55") (name "unconnected-(H3-Pad2)") (class "Default")
      (node (ref "H3") (pin "2") (pinfunction "2_2") (pintype "input"))
    )
    (net (code "56") (name "unconnected-(H3-Pad3)") (class "Default")
      (node (ref "H3") (pin "3") (pinfunction "3_3") (pintype "input"))
    )
    (net (code "57") (name "unconnected-(H3-Pad4)") (class "Default")
      (node (ref "H3") (pin "4") (pinfunction "4_4") (pintype "input"))
    )
    (net (code "58") (name "unconnected-(H3-Pad5)") (class "Default")
      (node (ref "H3") (pin "5") (pinfunction "5_5") (pintype "input"))
    )
    (net (code "59") (name "unconnected-(H6-Pad2)") (class "Default")
      (node (ref "H6") (pin "2") (pinfunction "2_2") (pintype "input"))
    )
    (net (code "60") (name "unconnected-(H6-Pad3)") (class "Default")
      (node (ref "H6") (pin "3") (pinfunction "3_3") (pintype "input"))
    )
    (net (code "61") (name "unconnected-(H6-Pad4)") (class "Default")
      (node (ref "H6") (pin "4") (pinfunction "4_4") (pintype "input"))
    )
    (net (code "62") (name "unconnected-(H6-Pad5)") (class "Default")
      (node (ref "H6") (pin "5") (pinfunction "5_5") (pintype "input"))
    )
    (net (code "63") (name "unconnected-(H11-Pad2)") (class "Default")
      (node (ref "H11") (pin "2") (pinfunction "2_2") (pintype "input"))
    )
    (net (code "64") (name "unconnected-(H11-Pad3)") (class "Default")
      (node (ref "H11") (pin "3") (pinfunction "3_3") (pintype "input"))
    )
    (net (code "65") (name "unconnected-(H11-Pad4)") (class "Default")
      (node (ref "H11") (pin "4") (pinfunction "4_4") (pintype "input"))
    )
    (net (code "66") (name "unconnected-(H11-Pad5)") (class "Default")
      (node (ref "H11") (pin "5") (pinfunction "5_5") (pintype "input"))
    )
    (net (code "67") (name "unconnected-(P2-Pad4)") (class "Default")
      (node (ref "P2") (pin "4") (pinfunction "4_4") (pintype "input"))
    )
    (net (code "68") (name "unconnected-(P2-Pad5)") (class "Default")
      (node (ref "P2") (pin "5") (pinfunction "5_5") (pintype "input"))
    )
    (net (code "69") (name "unconnected-(P3-Pad4)") (class "Default")
      (node (ref "P3") (pin "4") (pinfunction "4_4") (pintype "input"))
    )
    (net (code "70") (name "unconnected-(P3-Pad5)") (class "Default")
      (node (ref "P3") (pin "5") (pinfunction "5_5") (pintype "input"))
    )
    (net (code "71") (name "unconnected-(SW1-PadMT1)") (class "Default")
      (node (ref "SW1") (pin "MT1") (pinfunction "MT1_MT1") (pintype "unspecified"))
    )
    (net (code "72") (name "unconnected-(SW1-PadMT2)") (class "Default")
      (node (ref "SW1") (pin "MT2") (pinfunction "MT2_MT2") (pintype "unspecified"))
    )
  )
)
